# mcu.net
KiCad netlist of a schematic drawn in Altium Designer
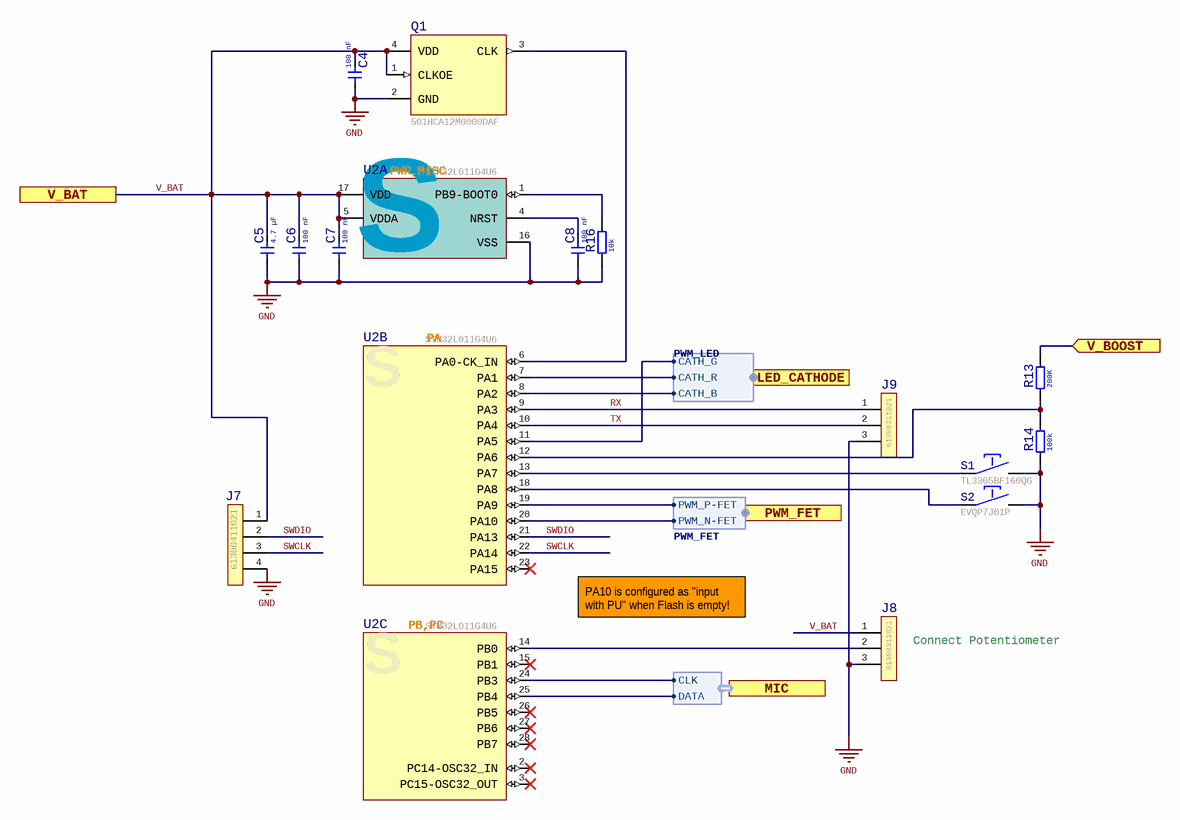
[diagram p0: mcu.SchDoc]

(export (version "E")
  (design (tool "Eeschema 10.0.6"))
  (components
    (comp (ref "C4")
      (value "100 nF")
      (footprint "1608C")
      (description "SMD ceramic capacitor")
      (fields (field (name "MANUFACTURER") "Samsung") (field (name "VOLTAGE") "16"))
      (libsource (lib "Contronix") (part "CAP-NP"))
    )
    (comp (ref "C5")
      (value "4.7 µF")
      (footprint "1608C")
      (description "SMD ceramic capacitor, X5R")
      (fields (field (name "MANUFACTURER") "Samsung") (field (name "VOLTAGE") "10"))
      (libsource (lib "Contronix") (part "CAP-NP"))
    )
    (comp (ref "C6")
      (value "100 nF")
      (footprint "1608C")
      (description "SMD ceramic capacitor")
      (fields (field (name "MANUFACTURER") "Samsung") (field (name "VOLTAGE") "16"))
      (libsource (lib "Contronix") (part "CAP-NP"))
    )
    (comp (ref "C7")
      (value "100 nF")
      (footprint "1608C")
      (description "SMD ceramic capacitor")
      (fields (field (name "MANUFACTURER") "Samsung") (field (name "VOLTAGE") "16"))
      (libsource (lib "Contronix") (part "CAP-NP"))
    )
    (comp (ref "C8")
      (value "100 nF")
      (footprint "1608C")
      (description "SMD ceramic capacitor")
      (fields (field (name "MANUFACTURER") "Samsung") (field (name "VOLTAGE") "16"))
      (libsource (lib "Contronix") (part "CAP-NP"))
    )
    (comp (ref "J7")
      (value "CON-04")
      (footprint "CON-04-1-254-H-T-PFL")
      (description "2.54 mm THT Stiftleiste einreihig abgewinkelt")
      (fields
        (field (name "MANUFACTURER P/N") "61300411021")
        (field (name "MANUFACTURER") "Würth Elektronik")
        (field (name "MANUFACTURER PART NUMBER") "61300411021")
      )
      (libsource (lib "Contronix") (part "CON-04"))
    )
    (comp (ref "J8")
      (value "CON-03")
      (footprint "CON-03-1-254-H-T-PFL")
      (description "2.54 mm THT Stiftleiste einreihig abgewinkelt WR-PHD")
      (fields
        (field (name "MANUFACTURER P/N") "61300311021")
        (field (name "MANUFACTURER") "Würth Elektronik")
        (field (name "MANUFACTURER PART NUMBER") "61300311021")
      )
      (libsource (lib "Contronix") (part "CON-03"))
    )
    (comp (ref "J9")
      (value "CON-03")
      (footprint "CON-03-1-254-H-T-PFL")
      (description "2.54 mm THT Stiftleiste einreihig abgewinkelt WR-PHD")
      (fields
        (field (name "MANUFACTURER P/N") "61300311021")
        (field (name "MANUFACTURER") "Würth Elektronik")
        (field (name "MANUFACTURER PART NUMBER") "61300311021")
      )
      (libsource (lib "Contronix") (part "CON-03"))
    )
    (comp (ref "Q1")
      (value "CRYS-OSC")
      (footprint "CRYS-OSC-2.5x2.0")
      (description "Crystal Oscillator")
      (fields
        (field (name "MANUFACTURER P/N") "501HCA12M0000DAF")
        (field (name "MANUFACTURER") "Silicon Laboratories Inc.")
        (field (name "MANUFACTURER PART NUMBER") "501HCA12M0000DAF")
      )
      (libsource (lib "Contronix") (part "CRYS-OSC"))
    )
    (comp (ref "R13")
      (value "200K")
      (footprint "1608R")
      (description "SMD resistor")
      (fields (field (name "MANUFACTURER") "Bourns Inc.") (field (name "TOLERANCE") "1%"))
      (libsource (lib "Contronix") (part "RES"))
    )
    (comp (ref "R14")
      (value "100k")
      (footprint "1608R")
      (description "SMD resistor")
      (fields (field (name "MANUFACTURER") "Panasonic - ECG") (field (name "TOLERANCE") "1%"))
      (libsource (lib "Contronix") (part "RES"))
    )
    (comp (ref "R16")
      (value "10k")
      (footprint "1608R")
      (description "SMD resistor")
      (fields (field (name "MANUFACTURER") "Panasonic - ECG") (field (name "TOLERANCE") "1%"))
      (libsource (lib "Contronix") (part "RES"))
    )
    (comp (ref "S1")
      (value "SWI-PU")
      (footprint "SWI-PU-TL3305BF")
      (description "SMD Push Button")
      (fields
        (field (name "MANUFACTURER P/N") "TL3305BF160QG")
        (field (name "MANUFACTURER") "E-Switch")
        (field (name "MANUFACTURER PART NUMBER") "TL3305BF160QG")
      )
      (libsource (lib "Contronix") (part "SWI-PU"))
    )
    (comp (ref "S2")
      (value "SWI-PU")
      (footprint "SWI-PU-RA-EVQP7(A+J)01P-REVERSEMOUNT")
      (description "SMD Push Button, Right Angle, straight terminals")
      (fields
        (field (name "MANUFACTURER P/N") "EVQP7J01P")
        (field (name "MANUFACTURER") "Panasonic")
        (field (name "MANUFACTURER PART NUMBER") "EVQP7J01P")
      )
      (libsource (lib "Contronix") (part "SWI-PU"))
    )
    (comp (ref "U2")
      (value "IC-STM32L011GxUx-QFN28")
      (footprint "IC-ST-UFQFN28")
      (fields
        (field (name "MANUFACTURER P/N") "STM32L011G4U6")
        (field (name "MANUFACTURER") "ST Microelectronics")
        (field (name "MANUFACTURER PART NUMBER") "STM32L011G4U6")
      )
      (libsource (lib "Contronix") (part "IC-STM32L011GxUx-QFN28"))
    )
  )
  (nets
    (net (code "4") (name "/CATH_B") (class "Default")
      (node (ref "U2") (pin "8") (pinfunction "PA2_8") (pintype "bidirectional"))
    )
    (net (code "5") (name "/CATH_G") (class "Default")
      (node (ref "U2") (pin "11") (pinfunction "PA5_11") (pintype "bidirectional"))
    )
    (net (code "6") (name "/CATH_R") (class "Default")
      (node (ref "U2") (pin "7") (pinfunction "PA1_7") (pintype "bidirectional"))
    )
    (net (code "7") (name "/CLK") (class "Default")
      (node (ref "U2") (pin "24") (pinfunction "PB3_24") (pintype "bidirectional"))
    )
    (net (code "8") (name "/DATA") (class "Default")
      (node (ref "U2") (pin "25") (pinfunction "PB4_25") (pintype "bidirectional"))
    )
    (net (code "9") (name "/PWM_N-FET") (class "Default")
      (node (ref "U2") (pin "20") (pinfunction "PA10_20") (pintype "bidirectional"))
    )
    (net (code "10") (name "/PWM_P-FET") (class "Default")
      (node (ref "U2") (pin "19") (pinfunction "PA9_19") (pintype "bidirectional"))
    )
    (net (code "11") (name "/RX") (class "Default")
      (node (ref "J9") (pin "1") (pinfunction "1_1") (pintype "passive"))
      (node (ref "U2") (pin "9") (pinfunction "PA3_9") (pintype "bidirectional"))
    )
    (net (code "12") (name "/SWCLK") (class "Default")
      (node (ref "J7") (pin "3") (pinfunction "3_3") (pintype "passive"))
      (node (ref "U2") (pin "22") (pinfunction "PA14_22") (pintype "bidirectional"))
    )
    (net (code "13") (name "/SWDIO") (class "Default")
      (node (ref "J7") (pin "2") (pinfunction "2_2") (pintype "passive"))
      (node (ref "U2") (pin "21") (pinfunction "PA13_21") (pintype "bidirectional"))
    )
    (net (code "14") (name "/TX") (class "Default")
      (node (ref "J9") (pin "2") (pinfunction "2_2") (pintype "passive"))
      (node (ref "U2") (pin "10") (pinfunction "PA4_10") (pintype "bidirectional"))
    )
    (net (code "15") (name "/V_BAT") (class "Default")
      (node (ref "C4") (pin "2") (pinfunction "2_2") (pintype "passive"))
      (node (ref "C5") (pin "2") (pinfunction "2_2") (pintype "passive"))
      (node (ref "C6") (pin "2") (pinfunction "2_2") (pintype "passive"))
      (node (ref "C7") (pin "2") (pinfunction "2_2") (pintype "passive"))
      (node (ref "J7") (pin "1") (pinfunction "1_1") (pintype "passive"))
      (node (ref "J8") (pin "1") (pinfunction "1_1") (pintype "passive"))
      (node (ref "Q1") (pin "1") (pinfunction "CLKOE_1") (pintype "input"))
      (node (ref "Q1") (pin "4") (pinfunction "VDD_4") (pintype "power_in"))
      (node (ref "U2") (pin "17") (pinfunction "VDD_17") (pintype "power_in"))
      (node (ref "U2") (pin "5") (pinfunction "VDDA_5") (pintype "power_in"))
    )
    (net (code "16") (name "/V_BOOST") (class "Default")
      (node (ref "R13") (pin "2") (pinfunction "2_2") (pintype "passive"))
    )
    (net (code "20") (name "GND") (class "Default")
      (node (ref "C4") (pin "1") (pinfunction "1_1") (pintype "passive"))
      (node (ref "C5") (pin "1") (pinfunction "1_1") (pintype "passive"))
      (node (ref "C6") (pin "1") (pinfunction "1_1") (pintype "passive"))
      (node (ref "C7") (pin "1") (pinfunction "1_1") (pintype "passive"))
      (node (ref "C8") (pin "1") (pinfunction "1_1") (pintype "passive"))
      (node (ref "J7") (pin "4") (pinfunction "4_4") (pintype "passive"))
      (node (ref "J8") (pin "3") (pinfunction "3_3") (pintype "passive"))
      (node (ref "J9") (pin "3") (pinfunction "3_3") (pintype "passive"))
      (node (ref "Q1") (pin "2") (pinfunction "GND_2") (pintype "passive"))
      (node (ref "R14") (pin "1") (pinfunction "1_1") (pintype "passive"))
      (node (ref "R16") (pin "1") (pinfunction "1_1") (pintype "passive"))
      (node (ref "S1") (pin "2") (pinfunction "2_2") (pintype "passive"))
      (node (ref "S2") (pin "2") (pinfunction "2_2") (pintype "passive"))
      (node (ref "U2") (pin "16") (pinfunction "VSS_16") (pintype "power_in"))
    )
    (net (code "21") (name "Net-(Q1-CLK)") (class "Default")
      (node (ref "Q1") (pin "3") (pinfunction "CLK_3") (pintype "output"))
      (node (ref "U2") (pin "6") (pinfunction "PA0-CK_IN_6") (pintype "bidirectional"))
    )
    (net (code "22") (name "Net-(U2A-NRST)") (class "Default")
      (node (ref "C8") (pin "2") (pinfunction "2_2") (pintype "passive"))
      (node (ref "U2") (pin "4") (pinfunction "NRST_4") (pintype "passive"))
    )
    (net (code "23") (name "Net-(U2A-PB9-BOOT0)") (class "Default")
      (node (ref "R16") (pin "2") (pinfunction "2_2") (pintype "passive"))
      (node (ref "U2") (pin "1") (pinfunction "PB9-BOOT0_1") (pintype "bidirectional"))
    )
    (net (code "24") (name "Net-(U2B-PA6)") (class "Default")
      (node (ref "R13") (pin "1") (pinfunction "1_1") (pintype "passive"))
      (node (ref "R14") (pin "2") (pinfunction "2_2") (pintype "passive"))
      (node (ref "U2") (pin "12") (pinfunction "PA6_12") (pintype "bidirectional"))
    )
    (net (code "25") (name "Net-(U2B-PA7)") (class "Default")
      (node (ref "S1") (pin "1") (pinfunction "1_1") (pintype "passive"))
      (node (ref "U2") (pin "13") (pinfunction "PA7_13") (pintype "bidirectional"))
    )
    (net (code "26") (name "Net-(U2B-PA8)") (class "Default")
      (node (ref "S2") (pin "1") (pinfunction "1_1") (pintype "passive"))
      (node (ref "U2") (pin "18") (pinfunction "PA8_18") (pintype "bidirectional"))
    )
    (net (code "27") (name "Net-(U2C-PB0)") (class "Default")
      (node (ref "J8") (pin "2") (pinfunction "2_2") (pintype "passive"))
      (node (ref "U2") (pin "14") (pinfunction "PB0_14") (pintype "bidirectional"))
    )
    (net (code "28") (name "unconnected-(U2B-PA15-Pad23)") (class "Default")
      (node (ref "U2") (pin "23") (pinfunction "PA15_23") (pintype "bidirectional+no_connect"))
    )
    (net (code "29") (name "unconnected-(U2C-PB1-Pad15)") (class "Default")
      (node (ref "U2") (pin "15") (pinfunction "PB1_15") (pintype "bidirectional+no_connect"))
    )
    (net (code "30") (name "unconnected-(U2C-PB5-Pad26)") (class "Default")
      (node (ref "U2") (pin "26") (pinfunction "PB5_26") (pintype "bidirectional+no_connect"))
    )
    (net (code "31") (name "unconnected-(U2C-PB6-Pad27)") (class "Default")
      (node (ref "U2") (pin "27") (pinfunction "PB6_27") (pintype "bidirectional+no_connect"))
    )
    (net (code "32") (name "unconnected-(U2C-PB7-Pad28)") (class "Default")
      (node (ref "U2") (pin "28") (pinfunction "PB7_28") (pintype "bidirectional+no_connect"))
    )
    (net (code "33") (name "unconnected-(U2C-PC14-OSC32_IN-Pad2)") (class "Default")
      (node (ref "U2") (pin "2") (pinfunction "PC14-OSC32_IN_2") (pintype "bidirectional+no_connect"))
    )
    (net (code "34") (name "unconnected-(U2C-PC15-OSC32_OUT-Pad3)") (class "Default")
      (node (ref "U2") (pin "3") (pinfunction "PC15-OSC32_OUT_3") (pintype "bidirectional+no_connect"))
    )
  )
)
